# LED_Youtube.net
KiCad netlist of a schematic drawn in Altium Designer
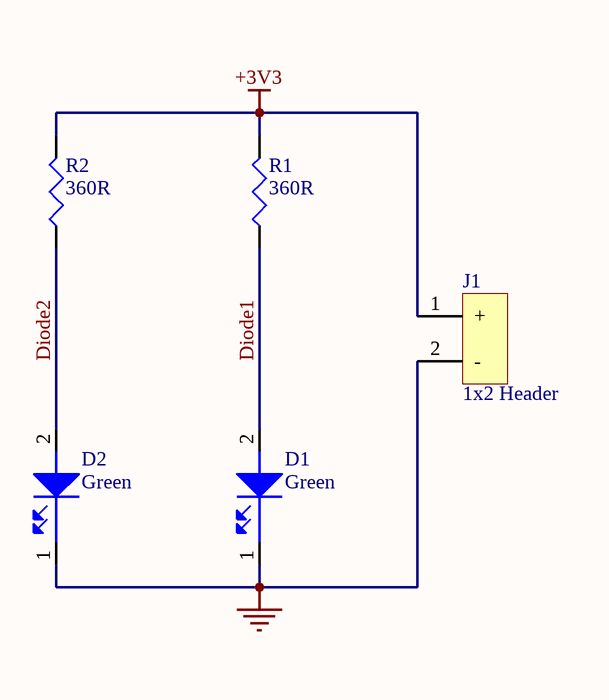
[diagram p0: LED_Youtube.SchDoc]

(export (version "E")
  (design (tool "Eeschema 10.0.6"))
  (components
    (comp (ref "D1")
      (value "Green")
      (footprint "LED0603G")
      (description "LED GREEN CLEAR CHIP 0603 SMD")
      (fields (field (name "MANUFACTURER") "VCC") (field (name "MANUFACTURER PART NUMBER") "LSM0603453V"))
      (libsource (lib "LED_Schlib") (part "LSM0603453V"))
    )
    (comp (ref "D2")
      (value "Green")
      (footprint "LED0603G")
      (description "LED GREEN CLEAR CHIP 0603 SMD")
      (fields (field (name "MANUFACTURER") "VCC") (field (name "MANUFACTURER PART NUMBER") "LSM0603453V"))
      (libsource (lib "LED_Schlib") (part "LSM0603453V"))
    )
    (comp (ref "J1")
      (value "1x2 Header")
      (footprint "HDR1x2")
      (description "CONN HEADER VERT 2POS 2.54MM")
      (fields (field (name "MANUFACTURER") "Molex") (field (name "MANUFACTURER PART NUMBER") "22-27-2021"))
      (libsource (lib "LED_Schlib") (part "22-27-2021"))
    )
    (comp (ref "R1")
      (value "360R")
      (footprint "R0805")
      (description "RES SMD 360 OHM 1% 1/8W 0805")
      (fields
        (field (name "MANUFACTURER") "Yageo Group")
        (field (name "MANUFACTURER PART NUMBER") "AC0805FR-07360RL")
      )
      (libsource (lib "LED_Schlib") (part "AC0805FR-07360RL"))
    )
    (comp (ref "R2")
      (value "360R")
      (footprint "R0805")
      (description "RES SMD 360 OHM 1% 1/8W 0805")
      (fields
        (field (name "MANUFACTURER") "Yageo Group")
        (field (name "MANUFACTURER PART NUMBER") "AC0805FR-07360RL")
      )
      (libsource (lib "LED_Schlib") (part "AC0805FR-07360RL"))
    )
  )
  (nets
    (net (code "1") (name "+3V3") (class "Default")
      (node (ref "J1") (pin "1") (pinfunction "+_1") (pintype "passive"))
      (node (ref "R1") (pin "2") (pinfunction "2_2") (pintype "passive"))
      (node (ref "R2") (pin "2") (pinfunction "2_2") (pintype "passive"))
    )
    (net (code "2") (name "/Diode1") (class "Default")
      (node (ref "D1") (pin "2") (pinfunction "2_2") (pintype "passive"))
      (node (ref "R1") (pin "1") (pinfunction "1_1") (pintype "passive"))
    )
    (net (code "3") (name "/Diode2") (class "Default")
      (node (ref "D2") (pin "2") (pinfunction "2_2") (pintype "passive"))
      (node (ref "R2") (pin "1") (pinfunction "1_1") (pintype "passive"))
    )
    (net (code "4") (name "GND") (class "Default")
      (node (ref "D1") (pin "1") (pinfunction "1_1") (pintype "passive"))
      (node (ref "D2") (pin "1") (pinfunction "1_1") (pintype "passive"))
      (node (ref "J1") (pin "2") (pinfunction "-_2") (pintype "passive"))
    )
  )
)
